# odroid_shield.net
KiCad netlist of a schematic drawn in EAGLE
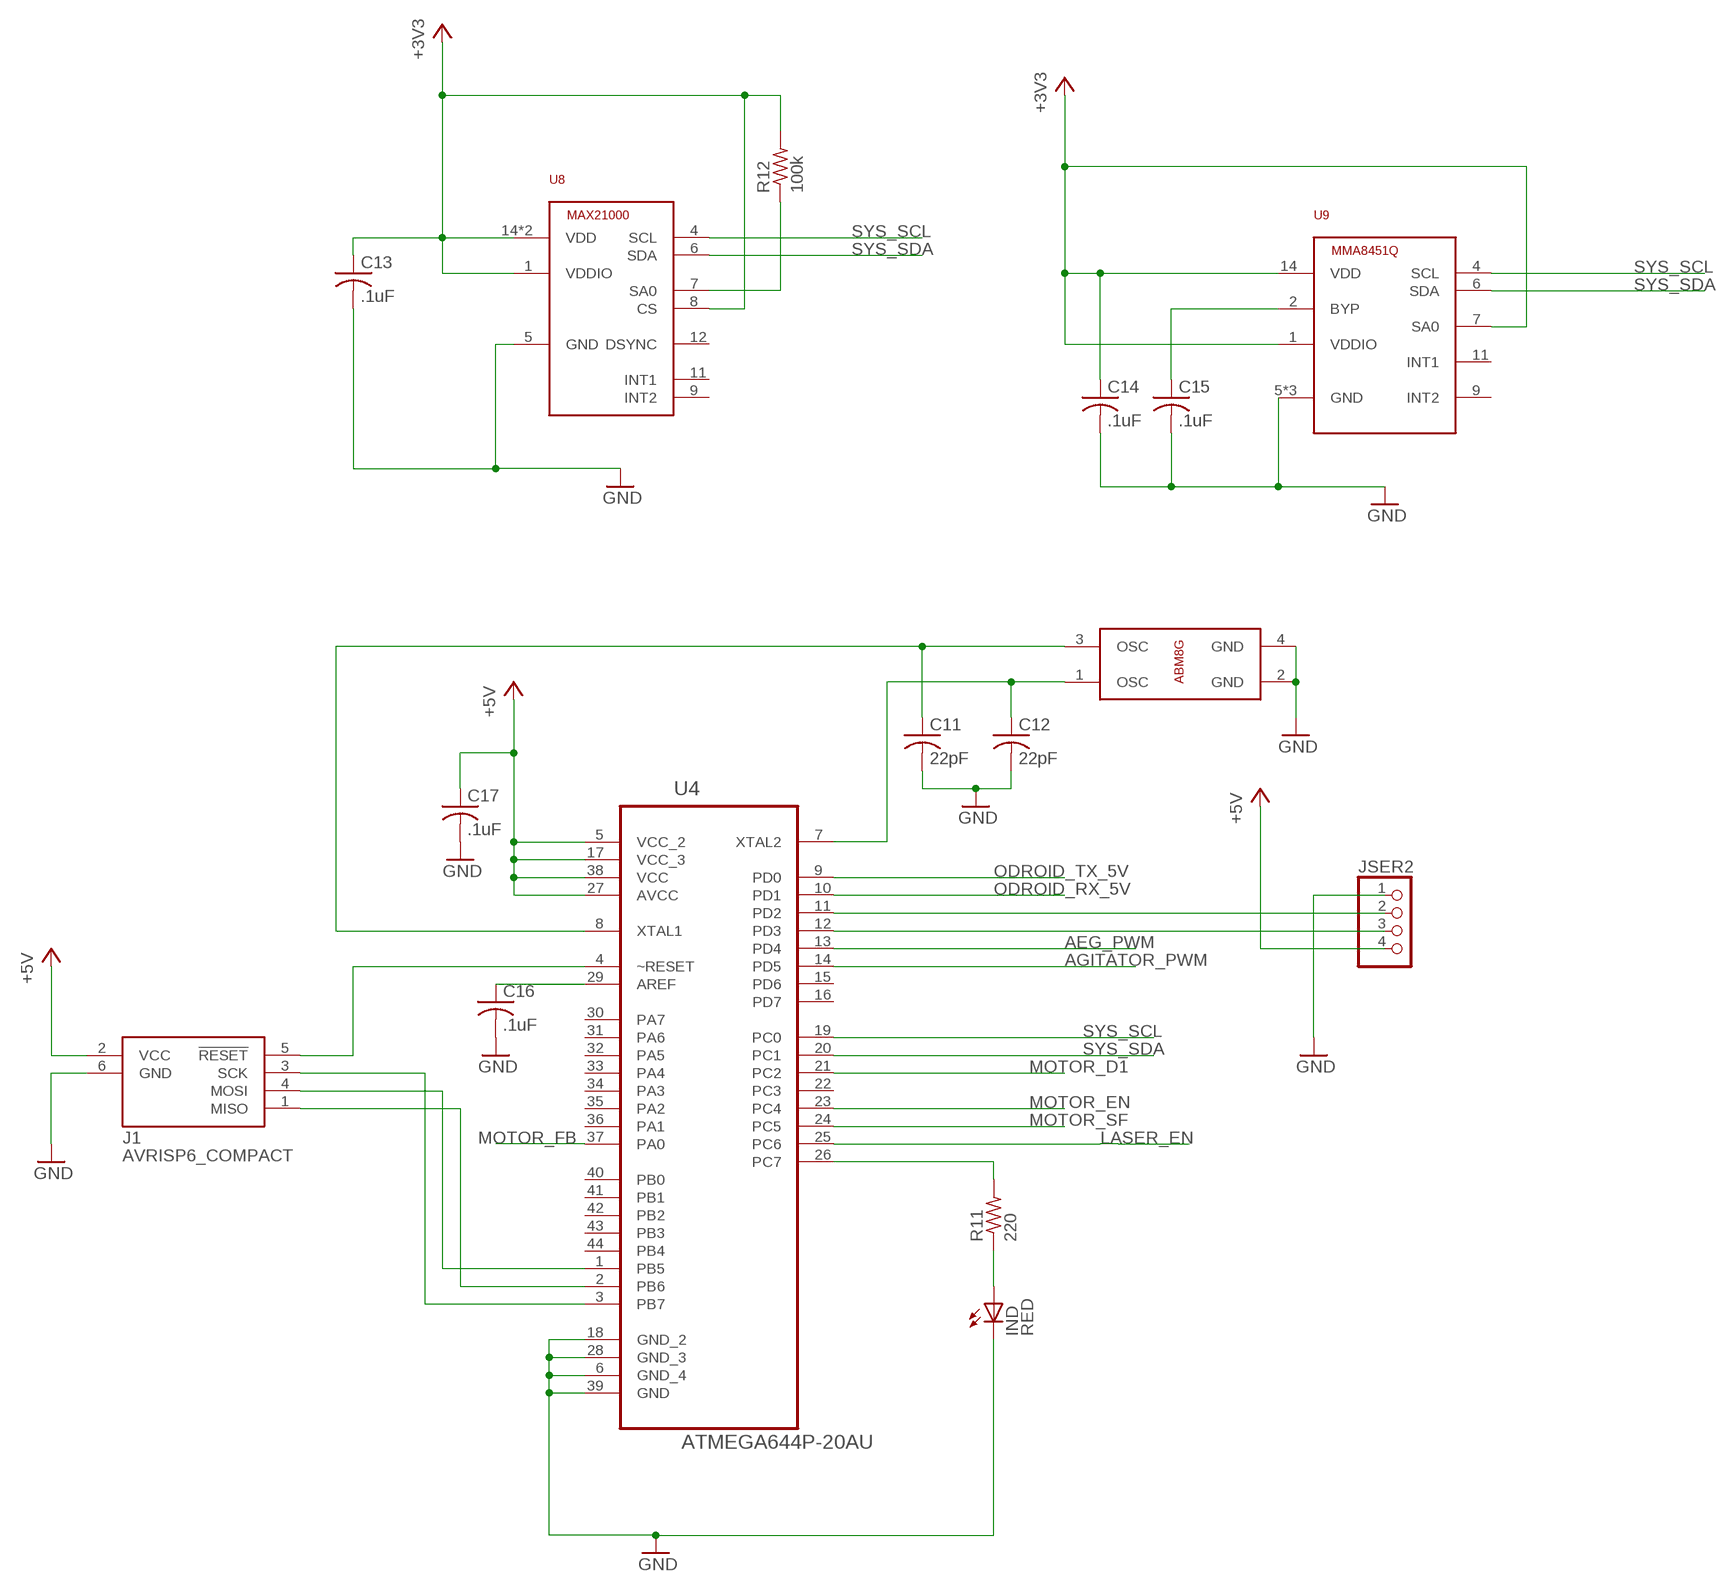
[diagram p0: schematic, sheet 1, part 1 of 2]
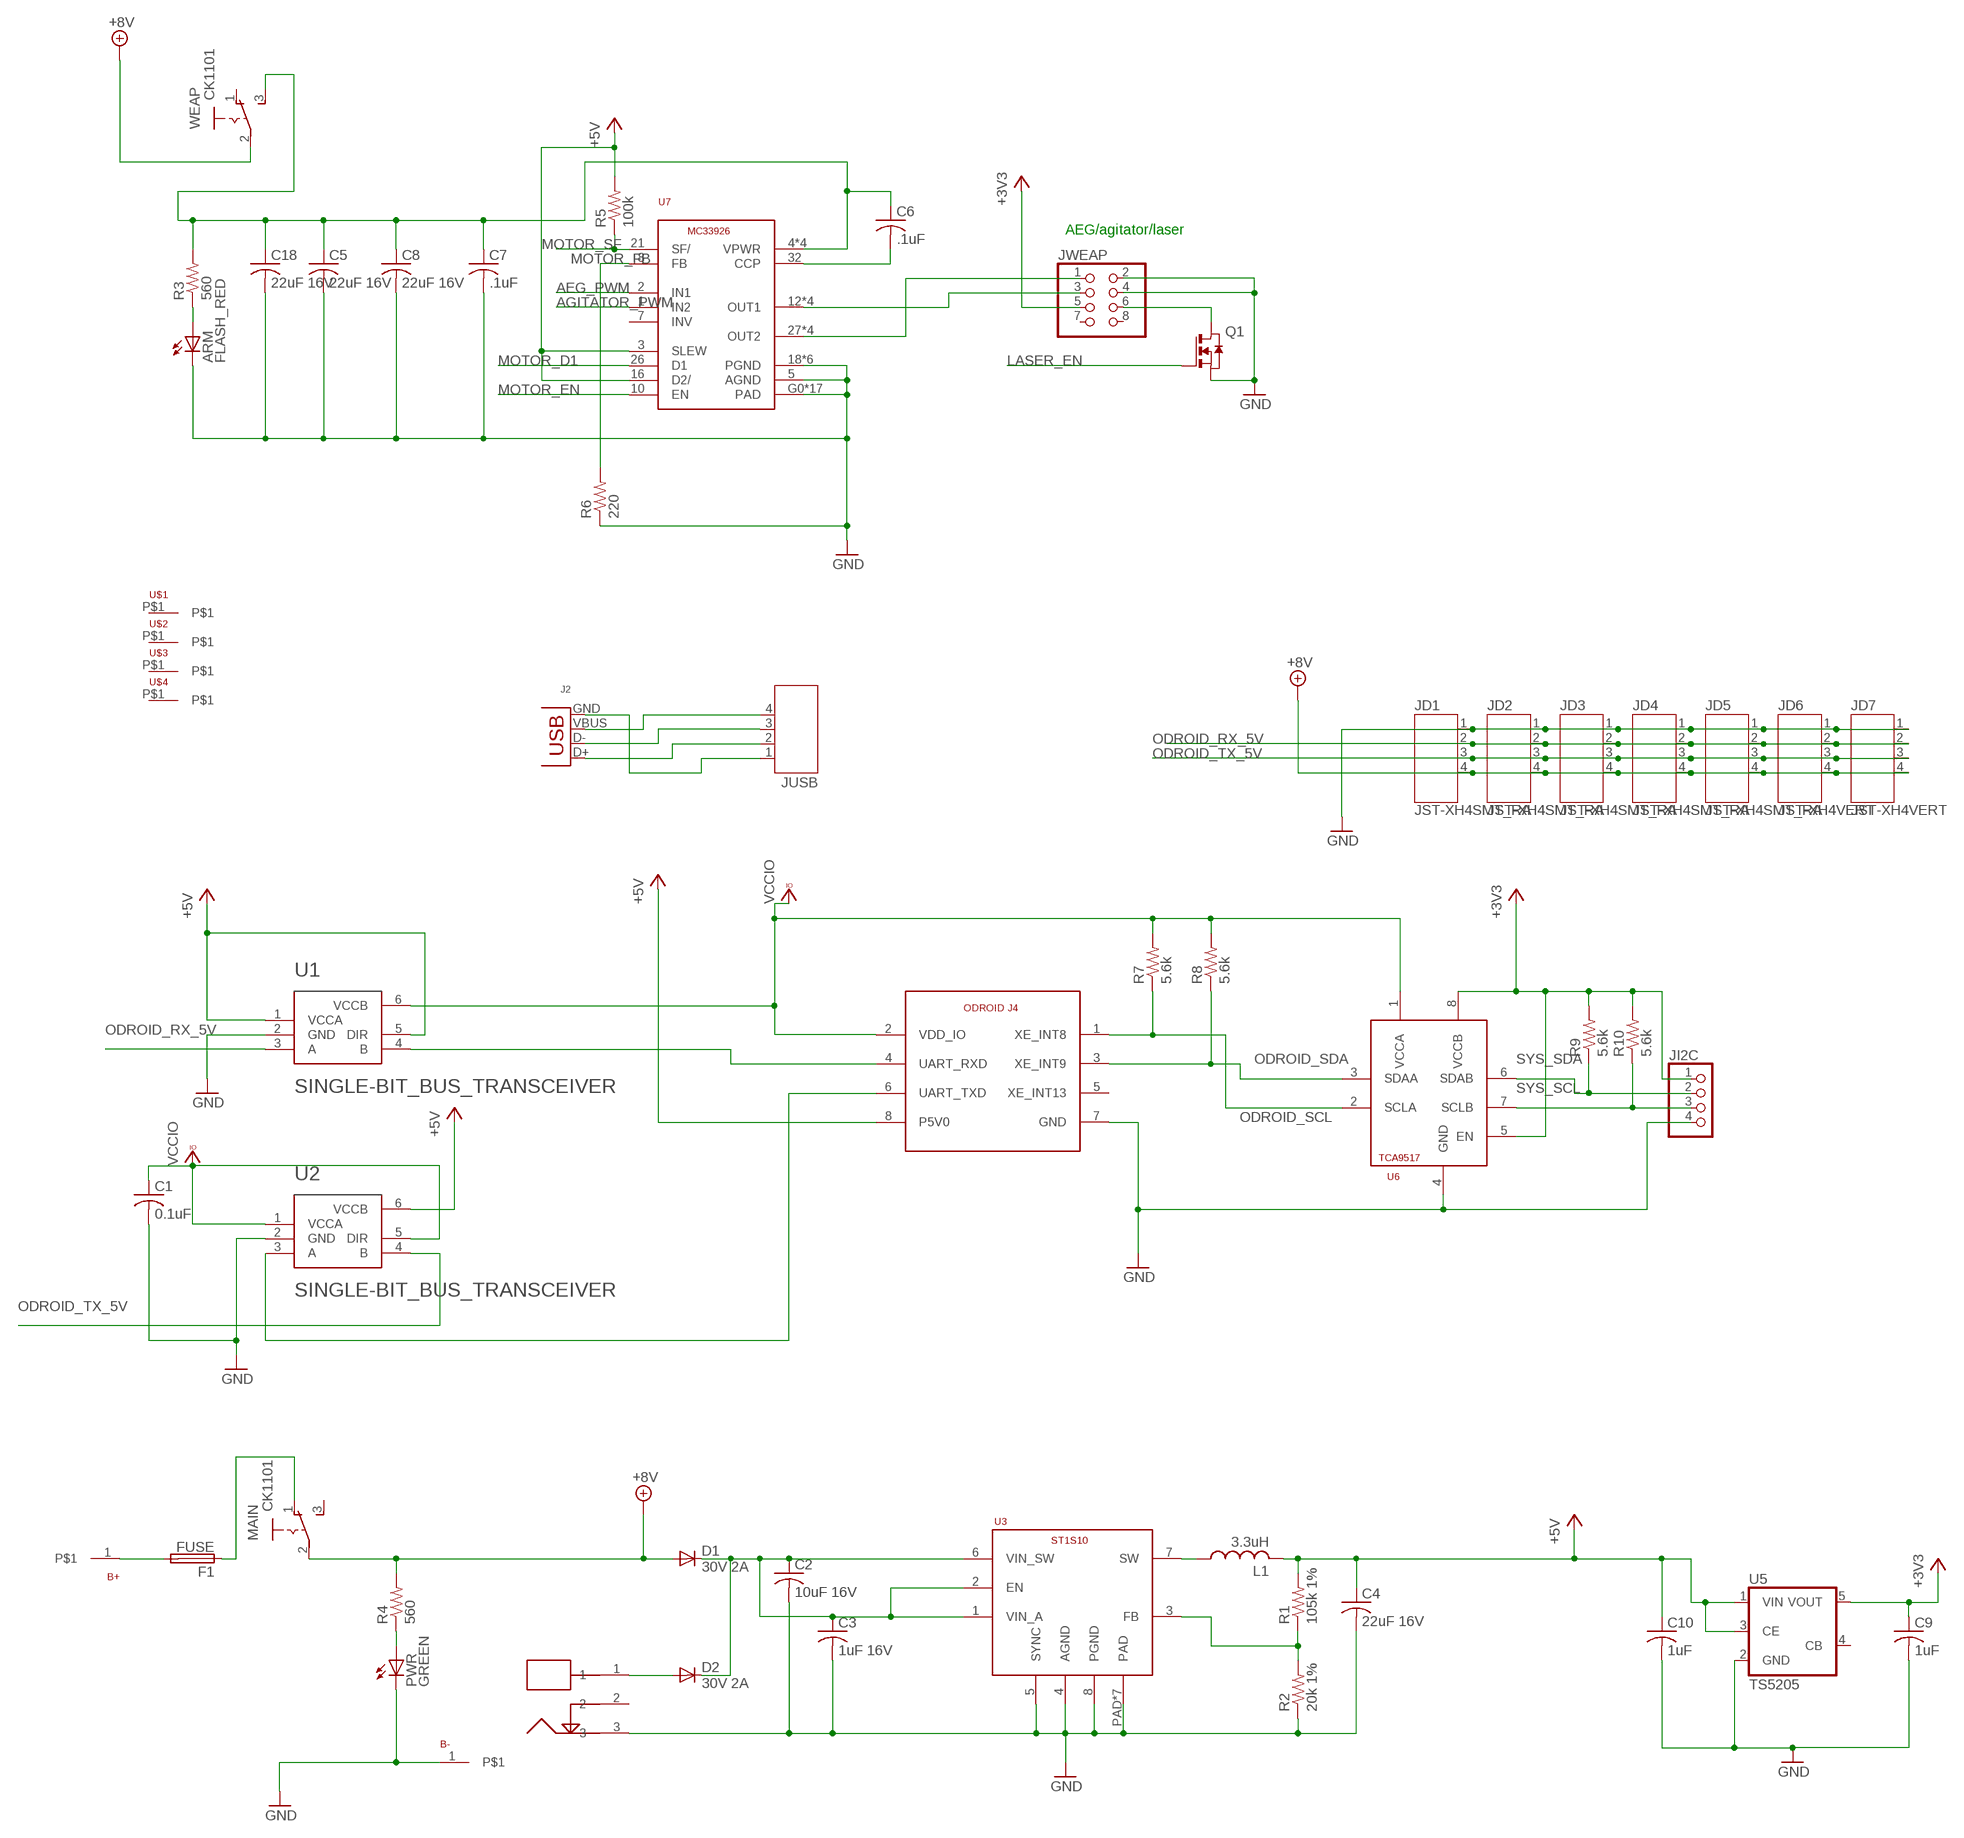
[diagram p1: schematic, sheet 1, part 2 of 2]

(export (version "E")
  (design (tool "Eeschema 10.0.6"))
  (components
    (comp (ref "ARM")
      (value "FLASH_RED")
      (footprint "eagle-import:LED5MM")
      (libsource (lib "eagle-import") (part "LED5MM"))
    )
    (comp (ref "B+")
      (value "BAT_TERM")
      (footprint "eagle-import:BAT_TERM")
      (libsource (lib "eagle-import") (part "BAT_TERM"))
    )
    (comp (ref "B-")
      (value "BAT_TERM")
      (footprint "eagle-import:BAT_TERM")
      (libsource (lib "eagle-import") (part "BAT_TERM"))
    )
    (comp (ref "C1")
      (value "0.1uF")
      (footprint "eagle-import:C0603")
      (libsource (lib "eagle-import") (part "C-USC0603"))
    )
    (comp (ref "C2")
      (value "10uF 16V")
      (footprint "eagle-import:C1206")
      (libsource (lib "eagle-import") (part "C-USC1206"))
    )
    (comp (ref "C3")
      (value "1uF 16V")
      (footprint "eagle-import:C0603")
      (libsource (lib "eagle-import") (part "C-USC0603"))
    )
    (comp (ref "C4")
      (value "22uF 16V")
      (footprint "eagle-import:C1210")
      (libsource (lib "eagle-import") (part "C-USC1210"))
    )
    (comp (ref "C5")
      (value "22uF 16V")
      (footprint "eagle-import:C1210")
      (libsource (lib "eagle-import") (part "C-USC1210"))
    )
    (comp (ref "C6")
      (value ".1uF")
      (footprint "eagle-import:C0603")
      (libsource (lib "eagle-import") (part "C-USC0603"))
    )
    (comp (ref "C7")
      (value ".1uF")
      (footprint "eagle-import:C0603")
      (libsource (lib "eagle-import") (part "C-USC0603"))
    )
    (comp (ref "C8")
      (value "22uF 16V")
      (footprint "eagle-import:C1210")
      (libsource (lib "eagle-import") (part "C-USC1210"))
    )
    (comp (ref "C9")
      (value "1uF")
      (footprint "eagle-import:C0603")
      (libsource (lib "eagle-import") (part "C-USC0603"))
    )
    (comp (ref "C10")
      (value "1uF")
      (footprint "eagle-import:C0603")
      (libsource (lib "eagle-import") (part "C-USC0603"))
    )
    (comp (ref "C11")
      (value "22pF")
      (footprint "eagle-import:C0603")
      (libsource (lib "eagle-import") (part "C-USC0603"))
    )
    (comp (ref "C12")
      (value "22pF")
      (footprint "eagle-import:C0603")
      (libsource (lib "eagle-import") (part "C-USC0603"))
    )
    (comp (ref "C13")
      (value ".1uF")
      (footprint "eagle-import:C0603")
      (libsource (lib "eagle-import") (part "C-USC0603"))
    )
    (comp (ref "C14")
      (value ".1uF")
      (footprint "eagle-import:C0603")
      (libsource (lib "eagle-import") (part "C-USC0603"))
    )
    (comp (ref "C15")
      (value ".1uF")
      (footprint "eagle-import:C0603")
      (libsource (lib "eagle-import") (part "C-USC0603"))
    )
    (comp (ref "C16")
      (value ".1uF")
      (footprint "eagle-import:C0603")
      (libsource (lib "eagle-import") (part "C-USC0603"))
    )
    (comp (ref "C17")
      (value ".1uF")
      (footprint "eagle-import:C0603")
      (libsource (lib "eagle-import") (part "C-USC0603"))
    )
    (comp (ref "C18")
      (value "22uF 16V")
      (footprint "eagle-import:C1210")
      (libsource (lib "eagle-import") (part "C-USC1210"))
    )
    (comp (ref "D1")
      (value "30V 2A")
      (footprint "eagle-import:CMS06")
      (libsource (lib "eagle-import") (part "DIODE-CMS06"))
    )
    (comp (ref "D2")
      (value "30V 2A")
      (footprint "eagle-import:CMS06")
      (libsource (lib "eagle-import") (part "DIODE-CMS06"))
    )
    (comp (ref "F1")
      (value "FUSE")
      (footprint "eagle-import:KEYSTONE_HORIZ_FUSE_CLIP")
      (libsource (lib "eagle-import") (part "FUSE"))
    )
    (comp (ref "IND")
      (value "RED")
      (footprint "eagle-import:CHIPLED_0805")
      (libsource (lib "eagle-import") (part "LEDCHIPLED_0805"))
    )
    (comp (ref "J1")
      (value "AVRISP6_COMPACT")
      (footprint "eagle-import:CON6P2R")
      (libsource (lib "eagle-import") (part "AVRISP6_COMPACT"))
    )
    (comp (ref "J2")
      (value "USB2MM")
      (footprint "eagle-import:1X04_2MM")
      (libsource (lib "eagle-import") (part "USB2MM"))
    )
    (comp (ref "J4")
      (value "ODROID_J4")
      (footprint "eagle-import:2X04_2MM")
      (libsource (lib "eagle-import") (part "ODROID_J4"))
    )
    (comp (ref "JD1")
      (value "JST-XH4SMT_RA")
      (footprint "eagle-import:JST_XH_SMT_RA_4")
      (libsource (lib "eagle-import") (part "JST-XH4SMT_RA"))
    )
    (comp (ref "JD2")
      (value "JST-XH4SMT_RA")
      (footprint "eagle-import:JST_XH_SMT_RA_4")
      (libsource (lib "eagle-import") (part "JST-XH4SMT_RA"))
    )
    (comp (ref "JD3")
      (value "JST-XH4SMT_RA")
      (footprint "eagle-import:JST_XH_SMT_RA_4")
      (libsource (lib "eagle-import") (part "JST-XH4SMT_RA"))
    )
    (comp (ref "JD4")
      (value "JST-XH4SMT_RA")
      (footprint "eagle-import:JST_XH_SMT_RA_4")
      (libsource (lib "eagle-import") (part "JST-XH4SMT_RA"))
    )
    (comp (ref "JD5")
      (value "JST-XH4SMT_RA")
      (footprint "eagle-import:JST_XH_SMT_RA_4")
      (libsource (lib "eagle-import") (part "JST-XH4SMT_RA"))
    )
    (comp (ref "JD6")
      (value "JST-XH4VERT")
      (footprint "eagle-import:JST_XH_VERT_4")
      (libsource (lib "eagle-import") (part "JST-XH4VERT"))
    )
    (comp (ref "JD7")
      (value "JST-XH4VERT")
      (footprint "eagle-import:JST_XH_VERT_4")
      (libsource (lib "eagle-import") (part "JST-XH4VERT"))
    )
    (comp (ref "JI2C")
      (value "PINHD-1X4")
      (footprint "eagle-import:1X04")
      (libsource (lib "eagle-import") (part "PINHD-1X4"))
    )
    (comp (ref "JSER2")
      (value "PINHD-1X4")
      (footprint "eagle-import:1X04")
      (libsource (lib "eagle-import") (part "PINHD-1X4"))
    )
    (comp (ref "JUSB")
      (value "JST-PH4")
      (footprint "eagle-import:JST-PH4")
      (libsource (lib "eagle-import") (part "JST-PH4"))
    )
    (comp (ref "JWEAP")
      (value "PINHD-2X4")
      (footprint "eagle-import:2X04")
      (libsource (lib "eagle-import") (part "PINHD-2X4"))
    )
    (comp (ref "L1")
      (value "3.3uH")
      (footprint "eagle-import:WURTH_74404042033")
      (libsource (lib "eagle-import") (part "L-USWURTH_74404042033"))
    )
    (comp (ref "MAIN")
      (value "CK1101")
      (footprint "eagle-import:CK1101C")
      (libsource (lib "eagle-import") (part "CK1101"))
    )
    (comp (ref "PWR")
      (value "GREEN")
      (footprint "eagle-import:CHIPLED_0805")
      (libsource (lib "eagle-import") (part "LEDCHIPLED_0805"))
    )
    (comp (ref "Q1")
      (value "NMOSSOT23")
      (footprint "eagle-import:SOT-23")
      (libsource (lib "eagle-import") (part "NMOSSOT23"))
    )
    (comp (ref "R1")
      (value "105k 1%")
      (footprint "eagle-import:R0603")
      (libsource (lib "eagle-import") (part "R-US_R0603"))
    )
    (comp (ref "R2")
      (value "20k 1%")
      (footprint "eagle-import:R0603")
      (libsource (lib "eagle-import") (part "R-US_R0603"))
    )
    (comp (ref "R3")
      (value "560")
      (footprint "eagle-import:R0603")
      (libsource (lib "eagle-import") (part "R-US_R0603"))
    )
    (comp (ref "R4")
      (value "560")
      (footprint "eagle-import:R0603")
      (libsource (lib "eagle-import") (part "R-US_R0603"))
    )
    (comp (ref "R5")
      (value "100k")
      (footprint "eagle-import:R0603")
      (libsource (lib "eagle-import") (part "R-US_R0603"))
    )
    (comp (ref "R6")
      (value "220")
      (footprint "eagle-import:R0603")
      (libsource (lib "eagle-import") (part "R-US_R0603"))
    )
    (comp (ref "R7")
      (value "5.6k")
      (footprint "eagle-import:R0603")
      (libsource (lib "eagle-import") (part "R-US_R0603"))
    )
    (comp (ref "R8")
      (value "5.6k")
      (footprint "eagle-import:R0603")
      (libsource (lib "eagle-import") (part "R-US_R0603"))
    )
    (comp (ref "R9")
      (value "5.6k")
      (footprint "eagle-import:R0603")
      (libsource (lib "eagle-import") (part "R-US_R0603"))
    )
    (comp (ref "R10")
      (value "5.6k")
      (footprint "eagle-import:R0603")
      (libsource (lib "eagle-import") (part "R-US_R0603"))
    )
    (comp (ref "R11")
      (value "220")
      (footprint "eagle-import:R0603")
      (libsource (lib "eagle-import") (part "R-US_R0603"))
    )
    (comp (ref "R12")
      (value "100k")
      (footprint "eagle-import:R0603")
      (libsource (lib "eagle-import") (part "R-US_R0603"))
    )
    (comp (ref "SHORE")
      (value "PJ-034ASMT")
      (footprint "eagle-import:CUI_PJ_015AH_SMT")
      (libsource (lib "eagle-import") (part "PJ-034ASMT"))
    )
    (comp (ref "U$1")
      (value "M3_HEX_MOUNT")
      (footprint "eagle-import:M3_HEX_MOUNT")
      (libsource (lib "eagle-import") (part "M3_HEX_MOUNT"))
    )
    (comp (ref "U$2")
      (value "M3_HEX_MOUNT")
      (footprint "eagle-import:M3_HEX_MOUNT")
      (libsource (lib "eagle-import") (part "M3_HEX_MOUNT"))
    )
    (comp (ref "U$3")
      (value "M3_HEX_MOUNT")
      (footprint "eagle-import:M3_HEX_MOUNT")
      (libsource (lib "eagle-import") (part "M3_HEX_MOUNT"))
    )
    (comp (ref "U$4")
      (value "M3_HEX_MOUNT")
      (footprint "eagle-import:M3_HEX_MOUNT")
      (libsource (lib "eagle-import") (part "M3_HEX_MOUNT"))
    )
    (comp (ref "U1")
      (value "SINGLE-BIT_BUS_TRANSCEIVER")
      (footprint "eagle-import:SOT23-6")
      (libsource (lib "eagle-import") (part "SINGLE-BIT_BUS_TRANSCEIVER"))
    )
    (comp (ref "U2")
      (value "SINGLE-BIT_BUS_TRANSCEIVER")
      (footprint "eagle-import:SOT23-6")
      (libsource (lib "eagle-import") (part "SINGLE-BIT_BUS_TRANSCEIVER"))
    )
    (comp (ref "U3")
      (value "ST1S10")
      (footprint "eagle-import:POWER_SO8")
      (libsource (lib "eagle-import") (part "ST1S10"))
    )
    (comp (ref "U4")
      (value "ATMEGA644P-20AU")
      (footprint "eagle-import:QFP80P1200X1200X120-44N")
      (libsource (lib "eagle-import") (part "ATMEGA644P-20AU"))
    )
    (comp (ref "U5")
      (value "TS5205")
      (footprint "eagle-import:SOT25")
      (libsource (lib "eagle-import") (part "TS5205"))
    )
    (comp (ref "U6")
      (value "TCA9517MSOP8")
      (footprint "eagle-import:MSOP8")
      (libsource (lib "eagle-import") (part "TCA9517MSOP8"))
    )
    (comp (ref "U7")
      (value "MC33926")
      (footprint "eagle-import:PQFN32")
      (libsource (lib "eagle-import") (part "MC33926"))
    )
    (comp (ref "U8")
      (value "MAX21000")
      (footprint "eagle-import:LGA16")
      (libsource (lib "eagle-import") (part "MAX21000"))
    )
    (comp (ref "U9")
      (value "MMA8451Q")
      (footprint "eagle-import:QFN16")
      (libsource (lib "eagle-import") (part "MMA8451Q"))
    )
    (comp (ref "U10")
      (value "ABM8G")
      (footprint "eagle-import:ABM8G")
      (libsource (lib "eagle-import") (part "ABM8G"))
    )
    (comp (ref "WEAP")
      (value "CK1101")
      (footprint "eagle-import:CK1101C")
      (libsource (lib "eagle-import") (part "CK1101"))
    )
  )
  (nets
    (net (code "1") (name "+3V3") (class "Default")
      (node (ref "C13") (pin "1") (pinfunction "1_1") (pintype "passive"))
      (node (ref "C14") (pin "1") (pinfunction "1_1") (pintype "passive"))
      (node (ref "C9") (pin "1") (pinfunction "1_1") (pintype "passive"))
      (node (ref "JI2C") (pin "1") (pinfunction "1_1") (pintype "passive"))
      (node (ref "JWEAP") (pin "5") (pinfunction "5_5") (pintype "passive"))
      (node (ref "R10") (pin "2") (pinfunction "2_2") (pintype "passive"))
      (node (ref "R12") (pin "2") (pinfunction "2_2") (pintype "passive"))
      (node (ref "R9") (pin "2") (pinfunction "2_2") (pintype "passive"))
      (node (ref "U5") (pin "5") (pinfunction "VOUT_5") (pintype "passive"))
      (node (ref "U6") (pin "5") (pinfunction "EN_5") (pintype "bidirectional"))
      (node (ref "U6") (pin "8") (pinfunction "VCCB_8") (pintype "bidirectional"))
      (node (ref "U8") (pin "1") (pinfunction "VDDIO_1") (pintype "bidirectional"))
      (node (ref "U8") (pin "14") (pinfunction "VDD_14") (pintype "bidirectional"))
      (node (ref "U8") (pin "15") (pinfunction "VDD_15") (pintype "bidirectional"))
      (node (ref "U8") (pin "8") (pinfunction "CS_8") (pintype "bidirectional"))
      (node (ref "U9") (pin "1") (pinfunction "VDDIO_1") (pintype "bidirectional"))
      (node (ref "U9") (pin "14") (pinfunction "VDD_14") (pintype "bidirectional"))
      (node (ref "U9") (pin "7") (pinfunction "SA0_7") (pintype "bidirectional"))
    )
    (net (code "2") (name "+5V") (class "Default")
      (node (ref "C10") (pin "1") (pinfunction "1_1") (pintype "passive"))
      (node (ref "C17") (pin "1") (pinfunction "1_1") (pintype "passive"))
      (node (ref "C4") (pin "1") (pinfunction "1_1") (pintype "passive"))
      (node (ref "J1") (pin "2") (pinfunction "VCC_2") (pintype "power_in"))
      (node (ref "J4") (pin "8") (pinfunction "P5V0_8") (pintype "bidirectional"))
      (node (ref "JSER2") (pin "4") (pinfunction "4_4") (pintype "passive"))
      (node (ref "L1") (pin "2") (pinfunction "2_2") (pintype "passive"))
      (node (ref "R1") (pin "2") (pinfunction "2_2") (pintype "passive"))
      (node (ref "R5") (pin "2") (pinfunction "2_2") (pintype "passive"))
      (node (ref "U1") (pin "1") (pinfunction "VCCA_1") (pintype "bidirectional"))
      (node (ref "U1") (pin "5") (pinfunction "DIR_5") (pintype "bidirectional"))
      (node (ref "U2") (pin "6") (pinfunction "VCCB_6") (pintype "bidirectional"))
      (node (ref "U4") (pin "17") (pinfunction "VCC_3_17") (pintype "power_in"))
      (node (ref "U4") (pin "27") (pinfunction "AVCC_27") (pintype "power_in"))
      (node (ref "U4") (pin "38") (pinfunction "VCC_38") (pintype "power_in"))
      (node (ref "U4") (pin "5") (pinfunction "VCC_2_5") (pintype "power_in"))
      (node (ref "U5") (pin "1") (pinfunction "VIN_1") (pintype "input"))
      (node (ref "U5") (pin "3") (pinfunction "CE_3") (pintype "input"))
      (node (ref "U7") (pin "16") (pinfunction "D2/_16") (pintype "bidirectional"))
      (node (ref "U7") (pin "3") (pinfunction "SLEW_3") (pintype "bidirectional"))
    )
    (net (code "3") (name "+8V") (class "Default")
      (node (ref "D1") (pin "1") (pinfunction "A_1") (pintype "passive"))
      (node (ref "JD1") (pin "4") (pinfunction "4_4") (pintype "passive"))
      (node (ref "JD2") (pin "4") (pinfunction "4_4") (pintype "passive"))
      (node (ref "JD3") (pin "4") (pinfunction "4_4") (pintype "passive"))
      (node (ref "JD4") (pin "4") (pinfunction "4_4") (pintype "passive"))
      (node (ref "JD5") (pin "4") (pinfunction "4_4") (pintype "passive"))
      (node (ref "JD6") (pin "4") (pinfunction "4_4") (pintype "passive"))
      (node (ref "JD7") (pin "4") (pinfunction "4_4") (pintype "passive"))
      (node (ref "MAIN") (pin "2") (pinfunction "P_2") (pintype "passive"))
      (node (ref "R4") (pin "2") (pinfunction "2_2") (pintype "passive"))
      (node (ref "WEAP") (pin "2") (pinfunction "P_2") (pintype "passive"))
    )
    (net (code "4") (name "/AEG_PWM") (class "Default")
      (node (ref "U4") (pin "13") (pinfunction "PD4_13") (pintype "bidirectional"))
      (node (ref "U7") (pin "2") (pinfunction "IN1_2") (pintype "bidirectional"))
    )
    (net (code "5") (name "/AGITATOR_PWM") (class "Default")
      (node (ref "U4") (pin "14") (pinfunction "PD5_14") (pintype "bidirectional"))
      (node (ref "U7") (pin "1") (pinfunction "IN2_1") (pintype "bidirectional"))
    )
    (net (code "6") (name "/LASER_EN") (class "Default")
      (node (ref "Q1") (pin "3") (pinfunction "G_3") (pintype "passive"))
      (node (ref "U4") (pin "25") (pinfunction "PC6_25") (pintype "bidirectional"))
    )
    (net (code "7") (name "/MOTOR_D1") (class "Default")
      (node (ref "U4") (pin "21") (pinfunction "PC2_21") (pintype "bidirectional"))
      (node (ref "U7") (pin "26") (pinfunction "D1_26") (pintype "bidirectional"))
    )
    (net (code "8") (name "/MOTOR_EN") (class "Default")
      (node (ref "U4") (pin "23") (pinfunction "PC4_23") (pintype "bidirectional"))
      (node (ref "U7") (pin "10") (pinfunction "EN_10") (pintype "bidirectional"))
    )
    (net (code "9") (name "/MOTOR_FB") (class "Default")
      (node (ref "R6") (pin "2") (pinfunction "2_2") (pintype "passive"))
      (node (ref "U4") (pin "37") (pinfunction "PA0_37") (pintype "bidirectional"))
      (node (ref "U7") (pin "8") (pinfunction "FB_8") (pintype "bidirectional"))
    )
    (net (code "10") (name "/MOTOR_SF") (class "Default")
      (node (ref "R5") (pin "1") (pinfunction "1_1") (pintype "passive"))
      (node (ref "U4") (pin "24") (pinfunction "PC5_24") (pintype "bidirectional"))
      (node (ref "U7") (pin "21") (pinfunction "SF/_21") (pintype "bidirectional"))
    )
    (net (code "11") (name "/ODROID_RX_5V") (class "Default")
      (node (ref "JD1") (pin "2") (pinfunction "2_2") (pintype "passive"))
      (node (ref "JD2") (pin "2") (pinfunction "2_2") (pintype "passive"))
      (node (ref "JD3") (pin "2") (pinfunction "2_2") (pintype "passive"))
      (node (ref "JD4") (pin "2") (pinfunction "2_2") (pintype "passive"))
      (node (ref "JD5") (pin "2") (pinfunction "2_2") (pintype "passive"))
      (node (ref "JD6") (pin "2") (pinfunction "2_2") (pintype "passive"))
      (node (ref "JD7") (pin "2") (pinfunction "2_2") (pintype "passive"))
      (node (ref "U1") (pin "3") (pinfunction "A_3") (pintype "bidirectional"))
      (node (ref "U4") (pin "10") (pinfunction "PD1_10") (pintype "bidirectional"))
    )
    (net (code "12") (name "/ODROID_SCL") (class "Default")
      (node (ref "J4") (pin "1") (pinfunction "XE_INT8_1") (pintype "bidirectional"))
      (node (ref "R7") (pin "1") (pinfunction "1_1") (pintype "passive"))
      (node (ref "U6") (pin "2") (pinfunction "SCLA_2") (pintype "bidirectional"))
    )
    (net (code "13") (name "/ODROID_SDA") (class "Default")
      (node (ref "J4") (pin "3") (pinfunction "XE_INT9_3") (pintype "bidirectional"))
      (node (ref "R8") (pin "1") (pinfunction "1_1") (pintype "passive"))
      (node (ref "U6") (pin "3") (pinfunction "SDAA_3") (pintype "bidirectional"))
    )
    (net (code "14") (name "/ODROID_TX_5V") (class "Default")
      (node (ref "JD1") (pin "3") (pinfunction "3_3") (pintype "passive"))
      (node (ref "JD2") (pin "3") (pinfunction "3_3") (pintype "passive"))
      (node (ref "JD3") (pin "3") (pinfunction "3_3") (pintype "passive"))
      (node (ref "JD4") (pin "3") (pinfunction "3_3") (pintype "passive"))
      (node (ref "JD5") (pin "3") (pinfunction "3_3") (pintype "passive"))
      (node (ref "JD6") (pin "3") (pinfunction "3_3") (pintype "passive"))
      (node (ref "JD7") (pin "3") (pinfunction "3_3") (pintype "passive"))
      (node (ref "U2") (pin "4") (pinfunction "B_4") (pintype "bidirectional"))
      (node (ref "U4") (pin "9") (pinfunction "PD0_9") (pintype "bidirectional"))
    )
    (net (code "15") (name "/SYS_SCL") (class "Default")
      (node (ref "JI2C") (pin "3") (pinfunction "3_3") (pintype "passive"))
      (node (ref "R10") (pin "1") (pinfunction "1_1") (pintype "passive"))
      (node (ref "U4") (pin "19") (pinfunction "PC0_19") (pintype "bidirectional"))
      (node (ref "U6") (pin "7") (pinfunction "SCLB_7") (pintype "bidirectional"))
      (node (ref "U8") (pin "4") (pinfunction "SCL_4") (pintype "bidirectional"))
      (node (ref "U9") (pin "4") (pinfunction "SCL_4") (pintype "bidirectional"))
    )
    (net (code "16") (name "/SYS_SDA") (class "Default")
      (node (ref "JI2C") (pin "2") (pinfunction "2_2") (pintype "passive"))
      (node (ref "R9") (pin "1") (pinfunction "1_1") (pintype "passive"))
      (node (ref "U4") (pin "20") (pinfunction "PC1_20") (pintype "bidirectional"))
      (node (ref "U6") (pin "6") (pinfunction "SDAB_6") (pintype "bidirectional"))
      (node (ref "U8") (pin "6") (pinfunction "SDA_6") (pintype "bidirectional"))
      (node (ref "U9") (pin "6") (pinfunction "SDA_6") (pintype "bidirectional"))
    )
    (net (code "17") (name "GND") (class "Default")
      (node (ref "ARM") (pin "K") (pinfunction "C_K") (pintype "passive"))
      (node (ref "B-") (pin "1") (pinfunction "P$1_1") (pintype "bidirectional"))
      (node (ref "C1") (pin "2") (pinfunction "2_2") (pintype "passive"))
      (node (ref "C10") (pin "2") (pinfunction "2_2") (pintype "passive"))
      (node (ref "C11") (pin "2") (pinfunction "2_2") (pintype "passive"))
      (node (ref "C12") (pin "2") (pinfunction "2_2") (pintype "passive"))
      (node (ref "C13") (pin "2") (pinfunction "2_2") (pintype "passive"))
      (node (ref "C14") (pin "2") (pinfunction "2_2") (pintype "passive"))
      (node (ref "C15") (pin "2") (pinfunction "2_2") (pintype "passive"))
      (node (ref "C16") (pin "2") (pinfunction "2_2") (pintype "passive"))
      (node (ref "C17") (pin "2") (pinfunction "2_2") (pintype "passive"))
      (node (ref "C18") (pin "2") (pinfunction "2_2") (pintype "passive"))
      (node (ref "C2") (pin "2") (pinfunction "2_2") (pintype "passive"))
      (node (ref "C3") (pin "2") (pinfunction "2_2") (pintype "passive"))
      (node (ref "C4") (pin "2") (pinfunction "2_2") (pintype "passive"))
      (node (ref "C5") (pin "2") (pinfunction "2_2") (pintype "passive"))
      (node (ref "C7") (pin "2") (pinfunction "2_2") (pintype "passive"))
      (node (ref "C8") (pin "2") (pinfunction "2_2") (pintype "passive"))
      (node (ref "C9") (pin "2") (pinfunction "2_2") (pintype "passive"))
      (node (ref "IND") (pin "C") (pinfunction "C_C") (pintype "passive"))
      (node (ref "J1") (pin "6") (pinfunction "GND_6") (pintype "power_in"))
      (node (ref "J4") (pin "7") (pinfunction "GND_7") (pintype "bidirectional"))
      (node (ref "JD1") (pin "1") (pinfunction "1_1") (pintype "passive"))
      (node (ref "JD2") (pin "1") (pinfunction "1_1") (pintype "passive"))
      (node (ref "JD3") (pin "1") (pinfunction "1_1") (pintype "passive"))
      (node (ref "JD4") (pin "1") (pinfunction "1_1") (pintype "passive"))
      (node (ref "JD5") (pin "1") (pinfunction "1_1") (pintype "passive"))
      (node (ref "JD6") (pin "1") (pinfunction "1_1") (pintype "passive"))
      (node (ref "JD7") (pin "1") (pinfunction "1_1") (pintype "passive"))
      (node (ref "JI2C") (pin "4") (pinfunction "4_4") (pintype "passive"))
      (node (ref "JSER2") (pin "1") (pinfunction "1_1") (pintype "passive"))
      (node (ref "JWEAP") (pin "2") (pinfunction "2_2") (pintype "passive"))
      (node (ref "JWEAP") (pin "4") (pinfunction "4_4") (pintype "passive"))
      (node (ref "PWR") (pin "C") (pinfunction "C_C") (pintype "passive"))
      (node (ref "Q1") (pin "2") (pinfunction "S_2") (pintype "passive"))
      (node (ref "R2") (pin "1") (pinfunction "1_1") (pintype "passive"))
      (node (ref "R6") (pin "1") (pinfunction "1_1") (pintype "passive"))
      (node (ref "SHORE") (pin "3") (pinfunction "3_3") (pintype "bidirectional"))
      (node (ref "U1") (pin "2") (pinfunction "GND_2") (pintype "bidirectional"))
      (node (ref "U10") (pin "2") (pinfunction "GND_2") (pintype "power_in"))
      (node (ref "U10") (pin "4") (pinfunction "GND_4") (pintype "bidirectional"))
      (node (ref "U2") (pin "2") (pinfunction "GND_2") (pintype "bidirectional"))
      (node (ref "U3") (pin "4") (pinfunction "AGND_4") (pintype "bidirectional"))
      (node (ref "U3") (pin "5") (pinfunction "SYNC_5") (pintype "bidirectional"))
      (node (ref "U3") (pin "8") (pinfunction "PGND_8") (pintype "bidirectional"))
      (node (ref "U3") (pin "PAD") (pinfunction "PAD_PAD") (pintype "bidirectional"))
      (node (ref "U3") (pin "PAD1") (pinfunction "PAD_PAD1") (pintype "bidirectional"))
      (node (ref "U3") (pin "PAD2") (pinfunction "PAD_PAD2") (pintype "bidirectional"))
      (node (ref "U3") (pin "PAD3") (pinfunction "PAD_PAD3") (pintype "bidirectional"))
      (node (ref "U3") (pin "PAD4") (pinfunction "PAD_PAD4") (pintype "bidirectional"))
      (node (ref "U3") (pin "PAD5") (pinfunction "PAD_PAD5") (pintype "bidirectional"))
      (node (ref "U3") (pin "PAD6") (pinfunction "PAD_PAD6") (pintype "bidirectional"))
      (node (ref "U4") (pin "18") (pinfunction "GND_2_18") (pintype "passive"))
      (node (ref "U4") (pin "28") (pinfunction "GND_3_28") (pintype "passive"))
      (node (ref "U4") (pin "39") (pinfunction "GND_39") (pintype "passive"))
      (node (ref "U4") (pin "6") (pinfunction "GND_4_6") (pintype "passive"))
      (node (ref "U5") (pin "2") (pinfunction "GND_2") (pintype "passive"))
      (node (ref "U6") (pin "4") (pinfunction "GND_4") (pintype "bidirectional"))
      (node (ref "U7") (pin "18") (pinfunction "PGND_18") (pintype "bidirectional"))
      (node (ref "U7") (pin "19") (pinfunction "PGND_19") (pintype "bidirectional"))
      (node (ref "U7") (pin "20") (pinfunction "PGND_20") (pintype "bidirectional"))
      (node (ref "U7") (pin "22") (pinfunction "PGND_22") (pintype "bidirectional"))
      (node (ref "U7") (pin "23") (pinfunction "PGND_23") (pintype "bidirectional"))
      (node (ref "U7") (pin "24") (pinfunction "PGND_24") (pintype "bidirectional"))
      (node (ref "U7") (pin "5") (pinfunction "AGND_5") (pintype "bidirectional"))
      (node (ref "U7") (pin "G0") (pinfunction "PAD_G0") (pintype "bidirectional"))
      (node (ref "U7") (pin "G1") (pinfunction "PAD_G1") (pintype "bidirectional"))
      (node (ref "U7") (pin "G10") (pinfunction "PAD_G10") (pintype "bidirectional"))
      (node (ref "U7") (pin "G11") (pinfunction "PAD_G11") (pintype "bidirectional"))
      (node (ref "U7") (pin "G12") (pinfunction "PAD_G12") (pintype "bidirectional"))
      (node (ref "U7") (pin "G13") (pinfunction "PAD_G13") (pintype "bidirectional"))
      (node (ref "U7") (pin "G14") (pinfunction "PAD_G14") (pintype "bidirectional"))
      (node (ref "U7") (pin "G15") (pinfunction "PAD_G15") (pintype "bidirectional"))
      (node (ref "U7") (pin "G16") (pinfunction "PAD_G16") (pintype "bidirectional"))
      (node (ref "U7") (pin "G2") (pinfunction "PAD_G2") (pintype "bidirectional"))
      (node (ref "U7") (pin "G3") (pinfunction "PAD_G3") (pintype "bidirectional"))
      (node (ref "U7") (pin "G4") (pinfunction "PAD_G4") (pintype "bidirectional"))
      (node (ref "U7") (pin "G5") (pinfunction "PAD_G5") (pintype "bidirectional"))
      (node (ref "U7") (pin "G6") (pinfunction "PAD_G6") (pintype "bidirectional"))
      (node (ref "U7") (pin "G7") (pinfunction "PAD_G7") (pintype "bidirectional"))
      (node (ref "U7") (pin "G8") (pinfunction "PAD_G8") (pintype "bidirectional"))
      (node (ref "U7") (pin "G9") (pinfunction "PAD_G9") (pintype "bidirectional"))
      (node (ref "U8") (pin "5") (pinfunction "GND_5") (pintype "bidirectional"))
      (node (ref "U9") (pin "10") (pinfunction "GND_10") (pintype "bidirectional"))
      (node (ref "U9") (pin "12") (pinfunction "GND_12") (pintype "bidirectional"))
      (node (ref "U9") (pin "5") (pinfunction "GND_5") (pintype "bidirectional"))
    )
    (net (code "18") (name "Net-(ARM-PadA)") (class "Default")
      (node (ref "ARM") (pin "A") (pinfunction "A_A") (pintype "passive"))
      (node (ref "R3") (pin "1") (pinfunction "1_1") (pintype "passive"))
    )
    (net (code "19") (name "Net-(B+-P$1)") (class "Default")
      (node (ref "B+") (pin "1") (pinfunction "P$1_1") (pintype "bidirectional"))
      (node (ref "F1") (pin "3") (pinfunction "2_3") (pintype "passive"))
      (node (ref "F1") (pin "4") (pinfunction "2_4") (pintype "passive"))
    )
    (net (code "20") (name "Net-(D1-C)") (class "Default")
      (node (ref "C2") (pin "1") (pinfunction "1_1") (pintype "passive"))
      (node (ref "C3") (pin "1") (pinfunction "1_1") (pintype "passive"))
      (node (ref "D1") (pin "2") (pinfunction "C_2") (pintype "passive"))
      (node (ref "D2") (pin "2") (pinfunction "C_2") (pintype "passive"))
      (node (ref "U3") (pin "1") (pinfunction "VIN_A_1") (pintype "bidirectional"))
      (node (ref "U3") (pin "2") (pinfunction "EN_2") (pintype "bidirectional"))
      (node (ref "U3") (pin "6") (pinfunction "VIN_SW_6") (pintype "bidirectional"))
    )
    (net (code "21") (name "Net-(D2-A)") (class "Default")
      (node (ref "D2") (pin "1") (pinfunction "A_1") (pintype "passive"))
      (node (ref "SHORE") (pin "1") (pinfunction "1_1") (pintype "bidirectional"))
    )
    (net (code "22") (name "Net-(IND-PadA)") (class "Default")
      (node (ref "IND") (pin "A") (pinfunction "A_A") (pintype "passive"))
      (node (ref "R11") (pin "1") (pinfunction "1_1") (pintype "passive"))
    )
    (net (code "23") (name "Net-(J1-MISO)") (class "Default")
      (node (ref "J1") (pin "1") (pinfunction "MISO_1") (pintype "input"))
      (node (ref "U4") (pin "2") (pinfunction "PB6_2") (pintype "bidirectional"))
    )
    (net (code "24") (name "Net-(J1-MOSI)") (class "Default")
      (node (ref "J1") (pin "4") (pinfunction "MOSI_4") (pintype "output"))
      (node (ref "U4") (pin "1") (pinfunction "PB5_1") (pintype "bidirectional"))
    )
    (net (code "25") (name "Net-(J1-SCK)") (class "Default")
      (node (ref "J1") (pin "3") (pinfunction "SCK_3") (pintype "output"))
      (node (ref "U4") (pin "3") (pinfunction "PB7_3") (pintype "bidirectional"))
    )
    (net (code "26") (name "Net-(J1-~{RESET})") (class "Default")
      (node (ref "J1") (pin "5") (pinfunction "~{RESET}_5") (pintype "output"))
      (node (ref "U4") (pin "4") (pinfunction "~{RESET}_4") (pintype "input"))
    )
    (net (code "27") (name "Net-(J2-PadD+)") (class "Default")
      (node (ref "J2") (pin "D+") (pinfunction "D+_D+") (pintype "bidirectional"))
      (node (ref "JUSB") (pin "2") (pinfunction "2_2") (pintype "passive"))
    )
    (net (code "28") (name "Net-(J2-PadD-)") (class "Default")
      (node (ref "J2") (pin "D-") (pinfunction "D-_D-") (pintype "bidirectional"))
      (node (ref "JUSB") (pin "3") (pinfunction "3_3") (pintype "passive"))
    )
    (net (code "29") (name "Net-(J2-PadGND)") (class "Default")
      (node (ref "J2") (pin "GND") (pinfunction "GND_GND") (pintype "bidirectional"))
      (node (ref "JUSB") (pin "1") (pinfunction "1_1") (pintype "passive"))
    )
    (net (code "30") (name "Net-(J2-PadVBUS)") (class "Default")
      (node (ref "J2") (pin "VBUS") (pinfunction "VBUS_VBUS") (pintype "bidirectional"))
      (node (ref "JUSB") (pin "4") (pinfunction "4_4") (pintype "passive"))
    )
    (net (code "31") (name "Net-(J4-UART_RXD)") (class "Default")
      (node (ref "J4") (pin "4") (pinfunction "UART_RXD_4") (pintype "bidirectional"))
      (node (ref "U1") (pin "4") (pinfunction "B_4") (pintype "bidirectional"))
    )
    (net (code "32") (name "Net-(J4-UART_TXD)") (class "Default")
      (node (ref "J4") (pin "6") (pinfunction "UART_TXD_6") (pintype "bidirectional"))
      (node (ref "U2") (pin "3") (pinfunction "A_3") (pintype "bidirectional"))
    )
    (net (code "33") (name "Net-(JWEAP-Pad1)") (class "Default")
      (node (ref "JWEAP") (pin "1") (pinfunction "1_1") (pintype "passive"))
      (node (ref "U7") (pin "27") (pinfunction "OUT2_27") (pintype "bidirectional"))
      (node (ref "U7") (pin "28") (pinfunction "OUT2_28") (pintype "bidirectional"))
      (node (ref "U7") (pin "29") (pinfunction "OUT2_29") (pintype "bidirectional"))
      (node (ref "U7") (pin "30") (pinfunction "OUT2_30") (pintype "bidirectional"))
    )
    (net (code "34") (name "Net-(JWEAP-Pad3)") (class "Default")
      (node (ref "JWEAP") (pin "3") (pinfunction "3_3") (pintype "passive"))
      (node (ref "U7") (pin "12") (pinfunction "OUT1_12") (pintype "bidirectional"))
      (node (ref "U7") (pin "13") (pinfunction "OUT1_13") (pintype "bidirectional"))
      (node (ref "U7") (pin "14") (pinfunction "OUT1_14") (pintype "bidirectional"))
      (node (ref "U7") (pin "15") (pinfunction "OUT1_15") (pintype "bidirectional"))
    )
    (net (code "35") (name "Net-(MAIN-O)") (class "Default")
      (node (ref "F1") (pin "1") (pinfunction "1_1") (pintype "passive"))
      (node (ref "F1") (pin "2") (pinfunction "1_2") (pintype "passive"))
      (node (ref "MAIN") (pin "1") (pinfunction "O_1") (pintype "passive"))
    )
    (net (code "36") (name "Net-(PWR-PadA)") (class "Default")
      (node (ref "PWR") (pin "A") (pinfunction "A_A") (pintype "passive"))
      (node (ref "R4") (pin "1") (pinfunction "1_1") (pintype "passive"))
    )
    (net (code "37") (name "Net-(Q1-D)") (class "Default")
      (node (ref "JWEAP") (pin "6") (pinfunction "6_6") (pintype "passive"))
      (node (ref "Q1") (pin "1") (pinfunction "D_1") (pintype "passive"))
    )
    (net (code "38") (name "Net-(U3-FB)") (class "Default")
      (node (ref "R1") (pin "1") (pinfunction "1_1") (pintype "passive"))
      (node (ref "R2") (pin "2") (pinfunction "2_2") (pintype "passive"))
      (node (ref "U3") (pin "3") (pinfunction "FB_3") (pintype "bidirectional"))
    )
    (net (code "39") (name "Net-(U3-SW)") (class "Default")
      (node (ref "L1") (pin "1") (pinfunction "1_1") (pintype "passive"))
      (node (ref "U3") (pin "7") (pinfunction "SW_7") (pintype "bidirectional"))
    )
    (net (code "40") (name "Net-(U4-AREF)") (class "Default")
      (node (ref "C16") (pin "1") (pinfunction "1_1") (pintype "passive"))
      (node (ref "U4") (pin "29") (pinfunction "AREF_29") (pintype "input"))
    )
    (net (code "41") (name "Net-(U4-PC7)") (class "Default")
      (node (ref "R11") (pin "2") (pinfunction "2_2") (pintype "passive"))
      (node (ref "U4") (pin "26") (pinfunction "PC7_26") (pintype "bidirectional"))
    )
    (net (code "42") (name "Net-(U4-PD2)") (class "Default")
      (node (ref "JSER2") (pin "2") (pinfunction "2_2") (pintype "passive"))
      (node (ref "U4") (pin "11") (pinfunction "PD2_11") (pintype "bidirectional"))
    )
    (net (code "43") (name "Net-(U4-PD3)") (class "Default")
      (node (ref "JSER2") (pin "3") (pinfunction "3_3") (pintype "passive"))
      (node (ref "U4") (pin "12") (pinfunction "PD3_12") (pintype "bidirectional"))
    )
    (net (code "44") (name "Net-(U4-XTAL1)") (class "Default")
      (node (ref "C11") (pin "1") (pinfunction "1_1") (pintype "passive"))
      (node (ref "U10") (pin "3") (pinfunction "OSC_3") (pintype "output"))
      (node (ref "U4") (pin "8") (pinfunction "XTAL1_8") (pintype "input"))
    )
    (net (code "45") (name "Net-(U4-XTAL2)") (class "Default")
      (node (ref "C12") (pin "1") (pinfunction "1_1") (pintype "passive"))
      (node (ref "U10") (pin "1") (pinfunction "OSC_1") (pintype "output"))
      (node (ref "U4") (pin "7") (pinfunction "XTAL2_7") (pintype "output"))
    )
    (net (code "46") (name "Net-(U7-CCP)") (class "Default")
      (node (ref "C6") (pin "2") (pinfunction "2_2") (pintype "passive"))
      (node (ref "U7") (pin "32") (pinfunction "CCP_32") (pintype "bidirectional"))
    )
    (net (code "47") (name "Net-(U8-SA0)") (class "Default")
      (node (ref "R12") (pin "1") (pinfunction "1_1") (pintype "passive"))
      (node (ref "U8") (pin "7") (pinfunction "SA0_7") (pintype "bidirectional"))
    )
    (net (code "48") (name "Net-(U9-BYP)") (class "Default")
      (node (ref "C15") (pin "1") (pinfunction "1_1") (pintype "passive"))
      (node (ref "U9") (pin "2") (pinfunction "BYP_2") (pintype "bidirectional"))
    )
    (net (code "49") (name "Net-(WEAP-S)") (class "Default")
      (node (ref "C18") (pin "1") (pinfunction "1_1") (pintype "passive"))
      (node (ref "C5") (pin "1") (pinfunction "1_1") (pintype "passive"))
      (node (ref "C6") (pin "1") (pinfunction "1_1") (pintype "passive"))
      (node (ref "C7") (pin "1") (pinfunction "1_1") (pintype "passive"))
      (node (ref "C8") (pin "1") (pinfunction "1_1") (pintype "passive"))
      (node (ref "R3") (pin "2") (pinfunction "2_2") (pintype "passive"))
      (node (ref "U7") (pin "11") (pinfunction "VPWR_11") (pintype "bidirectional"))
      (node (ref "U7") (pin "31") (pinfunction "VPWR_31") (pintype "bidirectional"))
      (node (ref "U7") (pin "4") (pinfunction "VPWR_4") (pintype "bidirectional"))
      (node (ref "U7") (pin "6") (pinfunction "VPWR_6") (pintype "bidirectional"))
      (node (ref "WEAP") (pin "3") (pinfunction "S_3") (pintype "passive"))
    )
    (net (code "50") (name "VCCIO") (class "Default")
      (node (ref "C1") (pin "1") (pinfunction "1_1") (pintype "passive"))
      (node (ref "J4") (pin "2") (pinfunction "VDD_IO_2") (pintype "bidirectional"))
      (node (ref "R7") (pin "2") (pinfunction "2_2") (pintype "passive"))
      (node (ref "R8") (pin "2") (pinfunction "2_2") (pintype "passive"))
      (node (ref "U1") (pin "6") (pinfunction "VCCB_6") (pintype "bidirectional"))
      (node (ref "U2") (pin "1") (pinfunction "VCCA_1") (pintype "bidirectional"))
      (node (ref "U2") (pin "5") (pinfunction "DIR_5") (pintype "bidirectional"))
      (node (ref "U6") (pin "1") (pinfunction "VCCA_1") (pintype "bidirectional"))
    )
    (net (code "51") (name "unconnected-(J4-XE_INT13-Pad5)") (class "Default")
      (node (ref "J4") (pin "5") (pinfunction "XE_INT13_5") (pintype "bidirectional"))
    )
    (net (code "52") (name "unconnected-(JWEAP-Pad7)") (class "Default")
      (node (ref "JWEAP") (pin "7") (pinfunction "7_7") (pintype "passive"))
    )
    (net (code "53") (name "unconnected-(JWEAP-Pad8)") (class "Default")
      (node (ref "JWEAP") (pin "8") (pinfunction "8_8") (pintype "passive"))
    )
    (net (code "54") (name "unconnected-(MAIN-S-Pad3)") (class "Default")
      (node (ref "MAIN") (pin "3") (pinfunction "S_3") (pintype "passive"))
    )
    (net (code "55") (name "unconnected-(SHORE-Pad2)") (class "Default")
      (node (ref "SHORE") (pin "2") (pinfunction "2_2") (pintype "bidirectional"))
    )
    (net (code "56") (name "unconnected-(U$1-PadP$1)") (class "Default")
      (node (ref "U$1") (pin "P$1") (pinfunction "P$1_P$1") (pintype "no_connect"))
    )
    (net (code "57") (name "unconnected-(U$2-PadP$1)") (class "Default")
      (node (ref "U$2") (pin "P$1") (pinfunction "P$1_P$1") (pintype "no_connect"))
    )
    (net (code "58") (name "unconnected-(U$3-PadP$1)") (class "Default")
      (node (ref "U$3") (pin "P$1") (pinfunction "P$1_P$1") (pintype "no_connect"))
    )
    (net (code "59") (name "unconnected-(U$4-PadP$1)") (class "Default")
      (node (ref "U$4") (pin "P$1") (pinfunction "P$1_P$1") (pintype "no_connect"))
    )
    (net (code "60") (name "unconnected-(U4-PA1-Pad36)") (class "Default")
      (node (ref "U4") (pin "36") (pinfunction "PA1_36") (pintype "bidirectional"))
    )
    (net (code "61") (name "unconnected-(U4-PA2-Pad35)") (class "Default")
      (node (ref "U4") (pin "35") (pinfunction "PA2_35") (pintype "bidirectional"))
    )
    (net (code "62") (name "unconnected-(U4-PA3-Pad34)") (class "Default")
      (node (ref "U4") (pin "34") (pinfunction "PA3_34") (pintype "bidirectional"))
    )
    (net (code "63") (name "unconnected-(U4-PA4-Pad33)") (class "Default")
      (node (ref "U4") (pin "33") (pinfunction "PA4_33") (pintype "bidirectional"))
    )
    (net (code "64") (name "unconnected-(U4-PA5-Pad32)") (class "Default")
      (node (ref "U4") (pin "32") (pinfunction "PA5_32") (pintype "bidirectional"))
    )
    (net (code "65") (name "unconnected-(U4-PA6-Pad31)") (class "Default")
      (node (ref "U4") (pin "31") (pinfunction "PA6_31") (pintype "bidirectional"))
    )
    (net (code "66") (name "unconnected-(U4-PA7-Pad30)") (class "Default")
      (node (ref "U4") (pin "30") (pinfunction "PA7_30") (pintype "bidirectional"))
    )
    (net (code "67") (name "unconnected-(U4-PB0-Pad40)") (class "Default")
      (node (ref "U4") (pin "40") (pinfunction "PB0_40") (pintype "bidirectional"))
    )
    (net (code "68") (name "unconnected-(U4-PB1-Pad41)") (class "Default")
      (node (ref "U4") (pin "41") (pinfunction "PB1_41") (pintype "bidirectional"))
    )
    (net (code "69") (name "unconnected-(U4-PB2-Pad42)") (class "Default")
      (node (ref "U4") (pin "42") (pinfunction "PB2_42") (pintype "bidirectional"))
    )
    (net (code "70") (name "unconnected-(U4-PB3-Pad43)") (class "Default")
      (node (ref "U4") (pin "43") (pinfunction "PB3_43") (pintype "bidirectional"))
    )
    (net (code "71") (name "unconnected-(U4-PB4-Pad44)") (class "Default")
      (node (ref "U4") (pin "44") (pinfunction "PB4_44") (pintype "bidirectional"))
    )
    (net (code "72") (name "unconnected-(U4-PC3-Pad22)") (class "Default")
      (node (ref "U4") (pin "22") (pinfunction "PC3_22") (pintype "bidirectional"))
    )
    (net (code "73") (name "unconnected-(U4-PD6-Pad15)") (class "Default")
      (node (ref "U4") (pin "15") (pinfunction "PD6_15") (pintype "bidirectional"))
    )
    (net (code "74") (name "unconnected-(U4-PD7-Pad16)") (class "Default")
      (node (ref "U4") (pin "16") (pinfunction "PD7_16") (pintype "bidirectional"))
    )
    (net (code "75") (name "unconnected-(U5-CB-Pad4)") (class "Default")
      (node (ref "U5") (pin "4") (pinfunction "CB_4") (pintype "input"))
    )
    (net (code "76") (name "unconnected-(U7-INV-Pad7)") (class "Default")
      (node (ref "U7") (pin "7") (pinfunction "INV_7") (pintype "bidirectional"))
    )
    (net (code "77") (name "unconnected-(U8-DSYNC-Pad12)") (class "Default")
      (node (ref "U8") (pin "12") (pinfunction "DSYNC_12") (pintype "bidirectional"))
    )
    (net (code "78") (name "unconnected-(U8-INT1-Pad11)") (class "Default")
      (node (ref "U8") (pin "11") (pinfunction "INT1_11") (pintype "bidirectional"))
    )
    (net (code "79") (name "unconnected-(U8-INT2-Pad9)") (class "Default")
      (node (ref "U8") (pin "9") (pinfunction "INT2_9") (pintype "bidirectional"))
    )
    (net (code "80") (name "unconnected-(U9-INT1-Pad11)") (class "Default")
      (node (ref "U9") (pin "11") (pinfunction "INT1_11") (pintype "bidirectional"))
    )
    (net (code "81") (name "unconnected-(U9-INT2-Pad9)") (class "Default")
      (node (ref "U9") (pin "9") (pinfunction "INT2_9") (pintype "bidirectional"))
    )
    (net (code "82") (name "unconnected-(WEAP-O-Pad1)") (class "Default")
      (node (ref "WEAP") (pin "1") (pinfunction "O_1") (pintype "passive"))
    )
  )
)
